# ESP32-1-System.net
KiCad netlist of a schematic drawn in Altium Designer
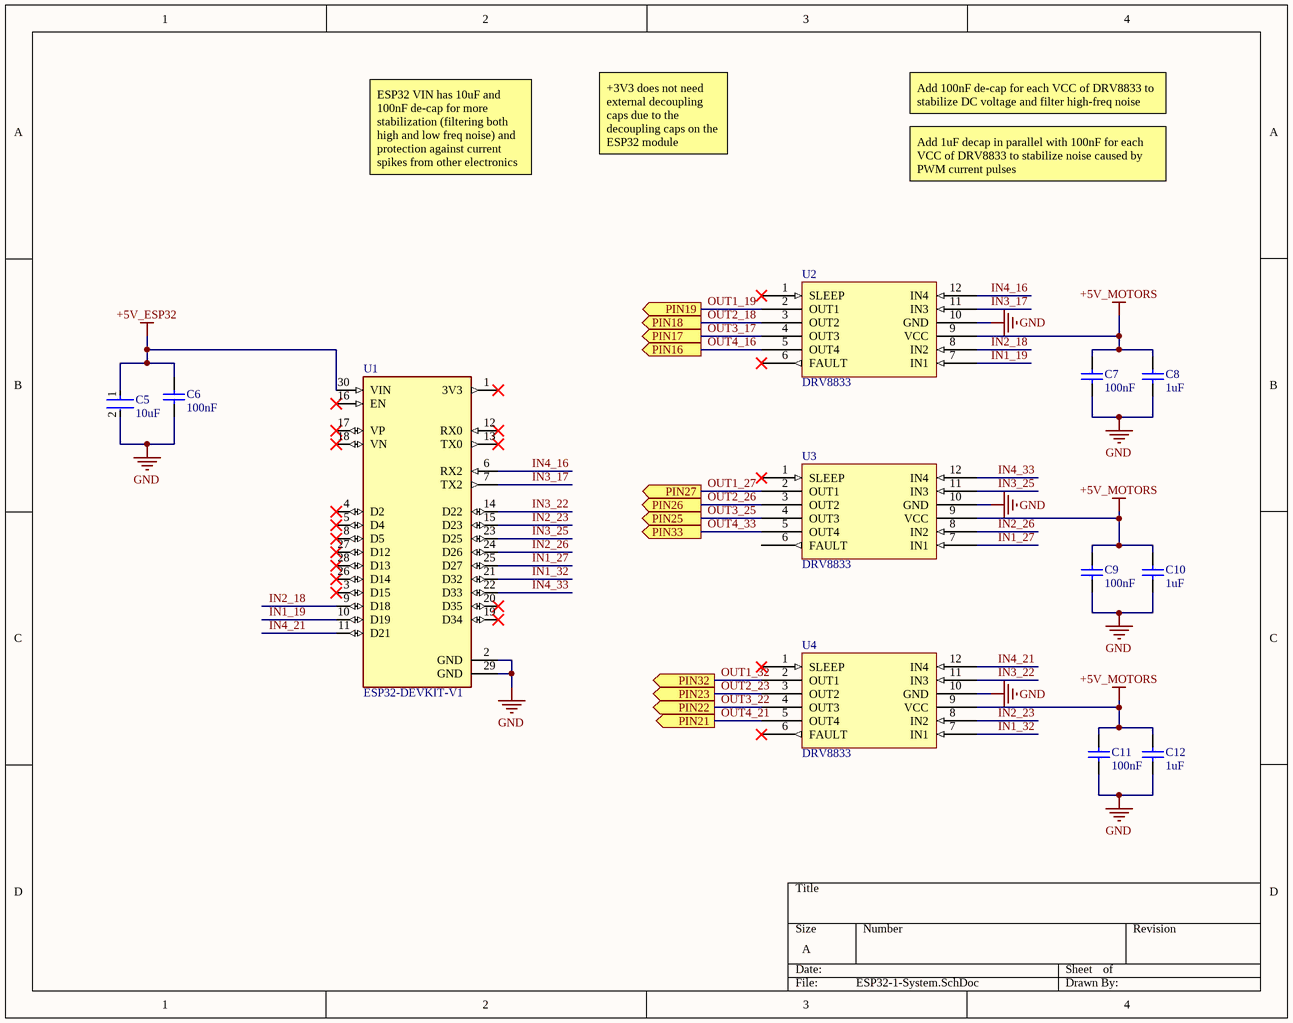
[diagram p0: ESP32-1-System.SchDoc]

(export (version "E")
  (design (tool "Eeschema 10.0.6"))
  (components
    (comp (ref "C5")
      (value "10uF")
      (footprint "FP-GCJ31C-0_4-IPC_C")
      (description "Cap Ceramic 10uF 35V X7T 10% SMD 1206 +125°C Embossed Plastic T/R")
      (libsource (lib "Altium Content Vault") (part "02cd4be3c70576c341d710602a673aa"))
    )
    (comp (ref "C6")
      (value "100nF")
      (footprint "CAPC1206(3216)170_L")
      (description "CAP 100nF 50V ±10% 1206 (3216 Metric) Thickness 1.7mm SMD")
      (fields (field (name "TOLERANCE") "Â±10%"))
      (libsource (lib "Altium Content Vault") (part "CAP"))
    )
    (comp (ref "C7")
      (value "100nF")
      (footprint "CAPC1206(3216)170_L")
      (description "CAP 100nF 50V ±10% 1206 (3216 Metric) Thickness 1.7mm SMD")
      (fields (field (name "TOLERANCE") "Â±10%"))
      (libsource (lib "Altium Content Vault") (part "CAP"))
    )
    (comp (ref "C8")
      (value "1uF")
      (footprint "CAPC1206(3216)170_L")
      (description "CAP 1uF 16V ±10% 1206 (3216 Metric) Thickness 1.7mm SMD")
      (fields (field (name "TOLERANCE") "Â±10%"))
      (libsource (lib "Altium Content Vault") (part "CAP"))
    )
    (comp (ref "C9")
      (value "100nF")
      (footprint "CAPC1206(3216)170_L")
      (description "CAP 100nF 50V ±10% 1206 (3216 Metric) Thickness 1.7mm SMD")
      (fields (field (name "TOLERANCE") "Â±10%"))
      (libsource (lib "Altium Content Vault") (part "CAP"))
    )
    (comp (ref "C10")
      (value "1uF")
      (footprint "CAPC1206(3216)170_L")
      (description "CAP 1uF 16V ±10% 1206 (3216 Metric) Thickness 1.7mm SMD")
      (fields (field (name "TOLERANCE") "Â±10%"))
      (libsource (lib "Altium Content Vault") (part "CAP"))
    )
    (comp (ref "C11")
      (value "100nF")
      (footprint "CAPC1206(3216)170_L")
      (description "CAP 100nF 50V ±10% 1206 (3216 Metric) Thickness 1.7mm SMD")
      (fields (field (name "TOLERANCE") "Â±10%"))
      (libsource (lib "Altium Content Vault") (part "CAP"))
    )
    (comp (ref "C12")
      (value "1uF")
      (footprint "CAPC1206(3216)170_L")
      (description "CAP 1uF 16V ±10% 1206 (3216 Metric) Thickness 1.7mm SMD")
      (fields (field (name "TOLERANCE") "Â±10%"))
      (libsource (lib "Altium Content Vault") (part "CAP"))
    )
    (comp (ref "U1")
      (value "ESP32-DEVKIT-V1")
      (footprint "MODULE_ESP32_DEVKIT_V1")
      (fields (field (name "MF") "Do it"))
      (libsource (lib "University of California, Riverside") (part "ESP32-DEVKIT-V1"))
    )
    (comp (ref "U2")
      (value "DRV8833")
      (footprint "PCBComponent_1")
      (description "1.5A 2-Channel DC Motor Drive Board Ultra Small Volume Motor Drive Module Input Voltage 3 to 10V")
      (libsource (lib "DRV8833") (part "DRV8833"))
    )
    (comp (ref "U3")
      (value "DRV8833")
      (footprint "PCBComponent_1")
      (description "1.5A 2-Channel DC Motor Drive Board Ultra Small Volume Motor Drive Module Input Voltage 3 to 10V")
      (libsource (lib "DRV8833") (part "DRV8833"))
    )
    (comp (ref "U4")
      (value "DRV8833")
      (footprint "PCBComponent_1")
      (description "1.5A 2-Channel DC Motor Drive Board Ultra Small Volume Motor Drive Module Input Voltage 3 to 10V")
      (libsource (lib "DRV8833") (part "DRV8833"))
    )
  )
  (nets
    (net (code "1") (name "+5V_ESP32") (class "Default")
      (node (ref "C5") (pin "1") (pinfunction "1_1") (pintype "passive"))
      (node (ref "C6") (pin "2") (pinfunction "2_2") (pintype "passive"))
      (node (ref "U1") (pin "30") (pinfunction "VIN_30") (pintype "input"))
    )
    (net (code "2") (name "+5V_MOTORS") (class "Default")
      (node (ref "C10") (pin "2") (pinfunction "2_2") (pintype "passive"))
      (node (ref "C11") (pin "2") (pinfunction "2_2") (pintype "passive"))
      (node (ref "C12") (pin "2") (pinfunction "2_2") (pintype "passive"))
      (node (ref "C7") (pin "2") (pinfunction "2_2") (pintype "passive"))
      (node (ref "C8") (pin "2") (pinfunction "2_2") (pintype "passive"))
      (node (ref "C9") (pin "2") (pinfunction "2_2") (pintype "passive"))
      (node (ref "U2") (pin "9") (pinfunction "VCC_9") (pintype "power_in"))
      (node (ref "U3") (pin "9") (pinfunction "VCC_9") (pintype "power_in"))
      (node (ref "U4") (pin "9") (pinfunction "VCC_9") (pintype "power_in"))
    )
    (net (code "3") (name "/IN1_19") (class "Default")
      (node (ref "U1") (pin "10") (pinfunction "D19_10") (pintype "bidirectional"))
      (node (ref "U2") (pin "7") (pinfunction "IN1_7") (pintype "input"))
    )
    (net (code "4") (name "/IN1_27") (class "Default")
      (node (ref "U1") (pin "25") (pinfunction "D27_25") (pintype "bidirectional"))
      (node (ref "U3") (pin "7") (pinfunction "IN1_7") (pintype "input"))
    )
    (net (code "5") (name "/IN1_32") (class "Default")
      (node (ref "U1") (pin "21") (pinfunction "D32_21") (pintype "bidirectional"))
      (node (ref "U4") (pin "7") (pinfunction "IN1_7") (pintype "input"))
    )
    (net (code "6") (name "/IN2_18") (class "Default")
      (node (ref "U1") (pin "9") (pinfunction "D18_9") (pintype "bidirectional"))
      (node (ref "U2") (pin "8") (pinfunction "IN2_8") (pintype "input"))
    )
    (net (code "7") (name "/IN2_23") (class "Default")
      (node (ref "U1") (pin "15") (pinfunction "D23_15") (pintype "bidirectional"))
      (node (ref "U4") (pin "8") (pinfunction "IN2_8") (pintype "input"))
    )
    (net (code "8") (name "/IN2_26") (class "Default")
      (node (ref "U1") (pin "24") (pinfunction "D26_24") (pintype "bidirectional"))
      (node (ref "U3") (pin "8") (pinfunction "IN2_8") (pintype "input"))
    )
    (net (code "9") (name "/IN3_17") (class "Default")
      (node (ref "U1") (pin "7") (pinfunction "TX2_7") (pintype "output"))
      (node (ref "U2") (pin "11") (pinfunction "IN3_11") (pintype "input"))
    )
    (net (code "10") (name "/IN3_22") (class "Default")
      (node (ref "U1") (pin "14") (pinfunction "D22_14") (pintype "bidirectional"))
      (node (ref "U4") (pin "11") (pinfunction "IN3_11") (pintype "input"))
    )
    (net (code "11") (name "/IN3_25") (class "Default")
      (node (ref "U1") (pin "23") (pinfunction "D25_23") (pintype "bidirectional"))
      (node (ref "U3") (pin "11") (pinfunction "IN3_11") (pintype "input"))
    )
    (net (code "12") (name "/IN4_16") (class "Default")
      (node (ref "U1") (pin "6") (pinfunction "RX2_6") (pintype "input"))
      (node (ref "U2") (pin "12") (pinfunction "IN4_12") (pintype "input"))
    )
    (net (code "13") (name "/IN4_21") (class "Default")
      (node (ref "U1") (pin "11") (pinfunction "D21_11") (pintype "bidirectional"))
      (node (ref "U4") (pin "12") (pinfunction "IN4_12") (pintype "input"))
    )
    (net (code "14") (name "/IN4_33") (class "Default")
      (node (ref "U1") (pin "22") (pinfunction "D33_22") (pintype "bidirectional"))
      (node (ref "U3") (pin "12") (pinfunction "IN4_12") (pintype "input"))
    )
    (net (code "15") (name "/OUT1_19") (class "Default")
      (node (ref "U2") (pin "2") (pinfunction "OUT1_2") (pintype "passive"))
    )
    (net (code "16") (name "/OUT1_27") (class "Default")
      (node (ref "U3") (pin "2") (pinfunction "OUT1_2") (pintype "passive"))
    )
    (net (code "17") (name "/OUT1_32") (class "Default")
      (node (ref "U4") (pin "2") (pinfunction "OUT1_2") (pintype "passive"))
    )
    (net (code "18") (name "/OUT2_18") (class "Default")
      (node (ref "U2") (pin "3") (pinfunction "OUT2_3") (pintype "passive"))
    )
    (net (code "19") (name "/OUT2_23") (class "Default")
      (node (ref "U4") (pin "3") (pinfunction "OUT2_3") (pintype "passive"))
    )
    (net (code "20") (name "/OUT2_26") (class "Default")
      (node (ref "U3") (pin "3") (pinfunction "OUT2_3") (pintype "passive"))
    )
    (net (code "21") (name "/OUT3_17") (class "Default")
      (node (ref "U2") (pin "4") (pinfunction "OUT3_4") (pintype "passive"))
    )
    (net (code "22") (name "/OUT3_22") (class "Default")
      (node (ref "U4") (pin "4") (pinfunction "OUT3_4") (pintype "passive"))
    )
    (net (code "23") (name "/OUT3_25") (class "Default")
      (node (ref "U3") (pin "4") (pinfunction "OUT3_4") (pintype "passive"))
    )
    (net (code "24") (name "/OUT4_16") (class "Default")
      (node (ref "U2") (pin "5") (pinfunction "OUT4_5") (pintype "passive"))
    )
    (net (code "25") (name "/OUT4_21") (class "Default")
      (node (ref "U4") (pin "5") (pinfunction "OUT4_5") (pintype "passive"))
    )
    (net (code "26") (name "/OUT4_33") (class "Default")
      (node (ref "U3") (pin "5") (pinfunction "OUT4_5") (pintype "passive"))
    )
    (net (code "27") (name "GND") (class "Default")
      (node (ref "C10") (pin "1") (pinfunction "1_1") (pintype "passive"))
      (node (ref "C11") (pin "1") (pinfunction "1_1") (pintype "passive"))
      (node (ref "C12") (pin "1") (pinfunction "1_1") (pintype "passive"))
      (node (ref "C5") (pin "2") (pinfunction "2_2") (pintype "passive"))
      (node (ref "C6") (pin "1") (pinfunction "1_1") (pintype "passive"))
      (node (ref "C7") (pin "1") (pinfunction "1_1") (pintype "passive"))
      (node (ref "C8") (pin "1") (pinfunction "1_1") (pintype "passive"))
      (node (ref "C9") (pin "1") (pinfunction "1_1") (pintype "passive"))
      (node (ref "U1") (pin "2") (pinfunction "GND_2") (pintype "power_in"))
      (node (ref "U1") (pin "29") (pinfunction "GND_29") (pintype "power_in"))
      (node (ref "U2") (pin "10") (pinfunction "GND_10") (pintype "power_in"))
      (node (ref "U3") (pin "10") (pinfunction "GND_10") (pintype "power_in"))
      (node (ref "U4") (pin "10") (pinfunction "GND_10") (pintype "power_in"))
    )
    (net (code "28") (name "unconnected-(U1-3V3-Pad1)") (class "Default")
      (node (ref "U1") (pin "1") (pinfunction "3V3_1") (pintype "output+no_connect"))
    )
    (net (code "29") (name "unconnected-(U1-D2-Pad4)") (class "Default")
      (node (ref "U1") (pin "4") (pinfunction "D2_4") (pintype "bidirectional+no_connect"))
    )
    (net (code "30") (name "unconnected-(U1-D4-Pad5)") (class "Default")
      (node (ref "U1") (pin "5") (pinfunction "D4_5") (pintype "bidirectional+no_connect"))
    )
    (net (code "31") (name "unconnected-(U1-D5-Pad8)") (class "Default")
      (node (ref "U1") (pin "8") (pinfunction "D5_8") (pintype "bidirectional+no_connect"))
    )
    (net (code "32") (name "unconnected-(U1-D12-Pad27)") (class "Default")
      (node (ref "U1") (pin "27") (pinfunction "D12_27") (pintype "bidirectional+no_connect"))
    )
    (net (code "33") (name "unconnected-(U1-D13-Pad28)") (class "Default")
      (node (ref "U1") (pin "28") (pinfunction "D13_28") (pintype "bidirectional+no_connect"))
    )
    (net (code "34") (name "unconnected-(U1-D14-Pad26)") (class "Default")
      (node (ref "U1") (pin "26") (pinfunction "D14_26") (pintype "bidirectional+no_connect"))
    )
    (net (code "35") (name "unconnected-(U1-D15-Pad3)") (class "Default")
      (node (ref "U1") (pin "3") (pinfunction "D15_3") (pintype "bidirectional+no_connect"))
    )
    (net (code "36") (name "unconnected-(U1-D34-Pad19)") (class "Default")
      (node (ref "U1") (pin "19") (pinfunction "D34_19") (pintype "bidirectional+no_connect"))
    )
    (net (code "37") (name "unconnected-(U1-D35-Pad20)") (class "Default")
      (node (ref "U1") (pin "20") (pinfunction "D35_20") (pintype "bidirectional+no_connect"))
    )
    (net (code "38") (name "unconnected-(U1-EN-Pad16)") (class "Default")
      (node (ref "U1") (pin "16") (pinfunction "EN_16") (pintype "input+no_connect"))
    )
    (net (code "39") (name "unconnected-(U1-RX0-Pad12)") (class "Default")
      (node (ref "U1") (pin "12") (pinfunction "RX0_12") (pintype "input+no_connect"))
    )
    (net (code "40") (name "unconnected-(U1-TX0-Pad13)") (class "Default")
      (node (ref "U1") (pin "13") (pinfunction "TX0_13") (pintype "output+no_connect"))
    )
    (net (code "41") (name "unconnected-(U1-VN-Pad18)") (class "Default")
      (node (ref "U1") (pin "18") (pinfunction "VN_18") (pintype "bidirectional+no_connect"))
    )
    (net (code "42") (name "unconnected-(U1-VP-Pad17)") (class "Default")
      (node (ref "U1") (pin "17") (pinfunction "VP_17") (pintype "bidirectional+no_connect"))
    )
    (net (code "43") (name "unconnected-(U2-FAULT-Pad6)") (class "Default")
      (node (ref "U2") (pin "6") (pinfunction "FAULT_6") (pintype "output+no_connect"))
    )
    (net (code "44") (name "unconnected-(U2-SLEEP-Pad1)") (class "Default")
      (node (ref "U2") (pin "1") (pinfunction "SLEEP_1") (pintype "input+no_connect"))
    )
    (net (code "45") (name "unconnected-(U3-FAULT-Pad6)") (class "Default")
      (node (ref "U3") (pin "6") (pinfunction "FAULT_6") (pintype "output"))
    )
    (net (code "46") (name "unconnected-(U3-SLEEP-Pad1)") (class "Default")
      (node (ref "U3") (pin "1") (pinfunction "SLEEP_1") (pintype "input+no_connect"))
    )
    (net (code "47") (name "unconnected-(U4-FAULT-Pad6)") (class "Default")
      (node (ref "U4") (pin "6") (pinfunction "FAULT_6") (pintype "output+no_connect"))
    )
    (net (code "48") (name "unconnected-(U4-SLEEP-Pad1)") (class "Default")
      (node (ref "U4") (pin "1") (pinfunction "SLEEP_1") (pintype "input+no_connect"))
    )
  )
)
